# 03_-_28PINS_SCHEMATIC.net
KiCad netlist of a schematic drawn in Altium Designer
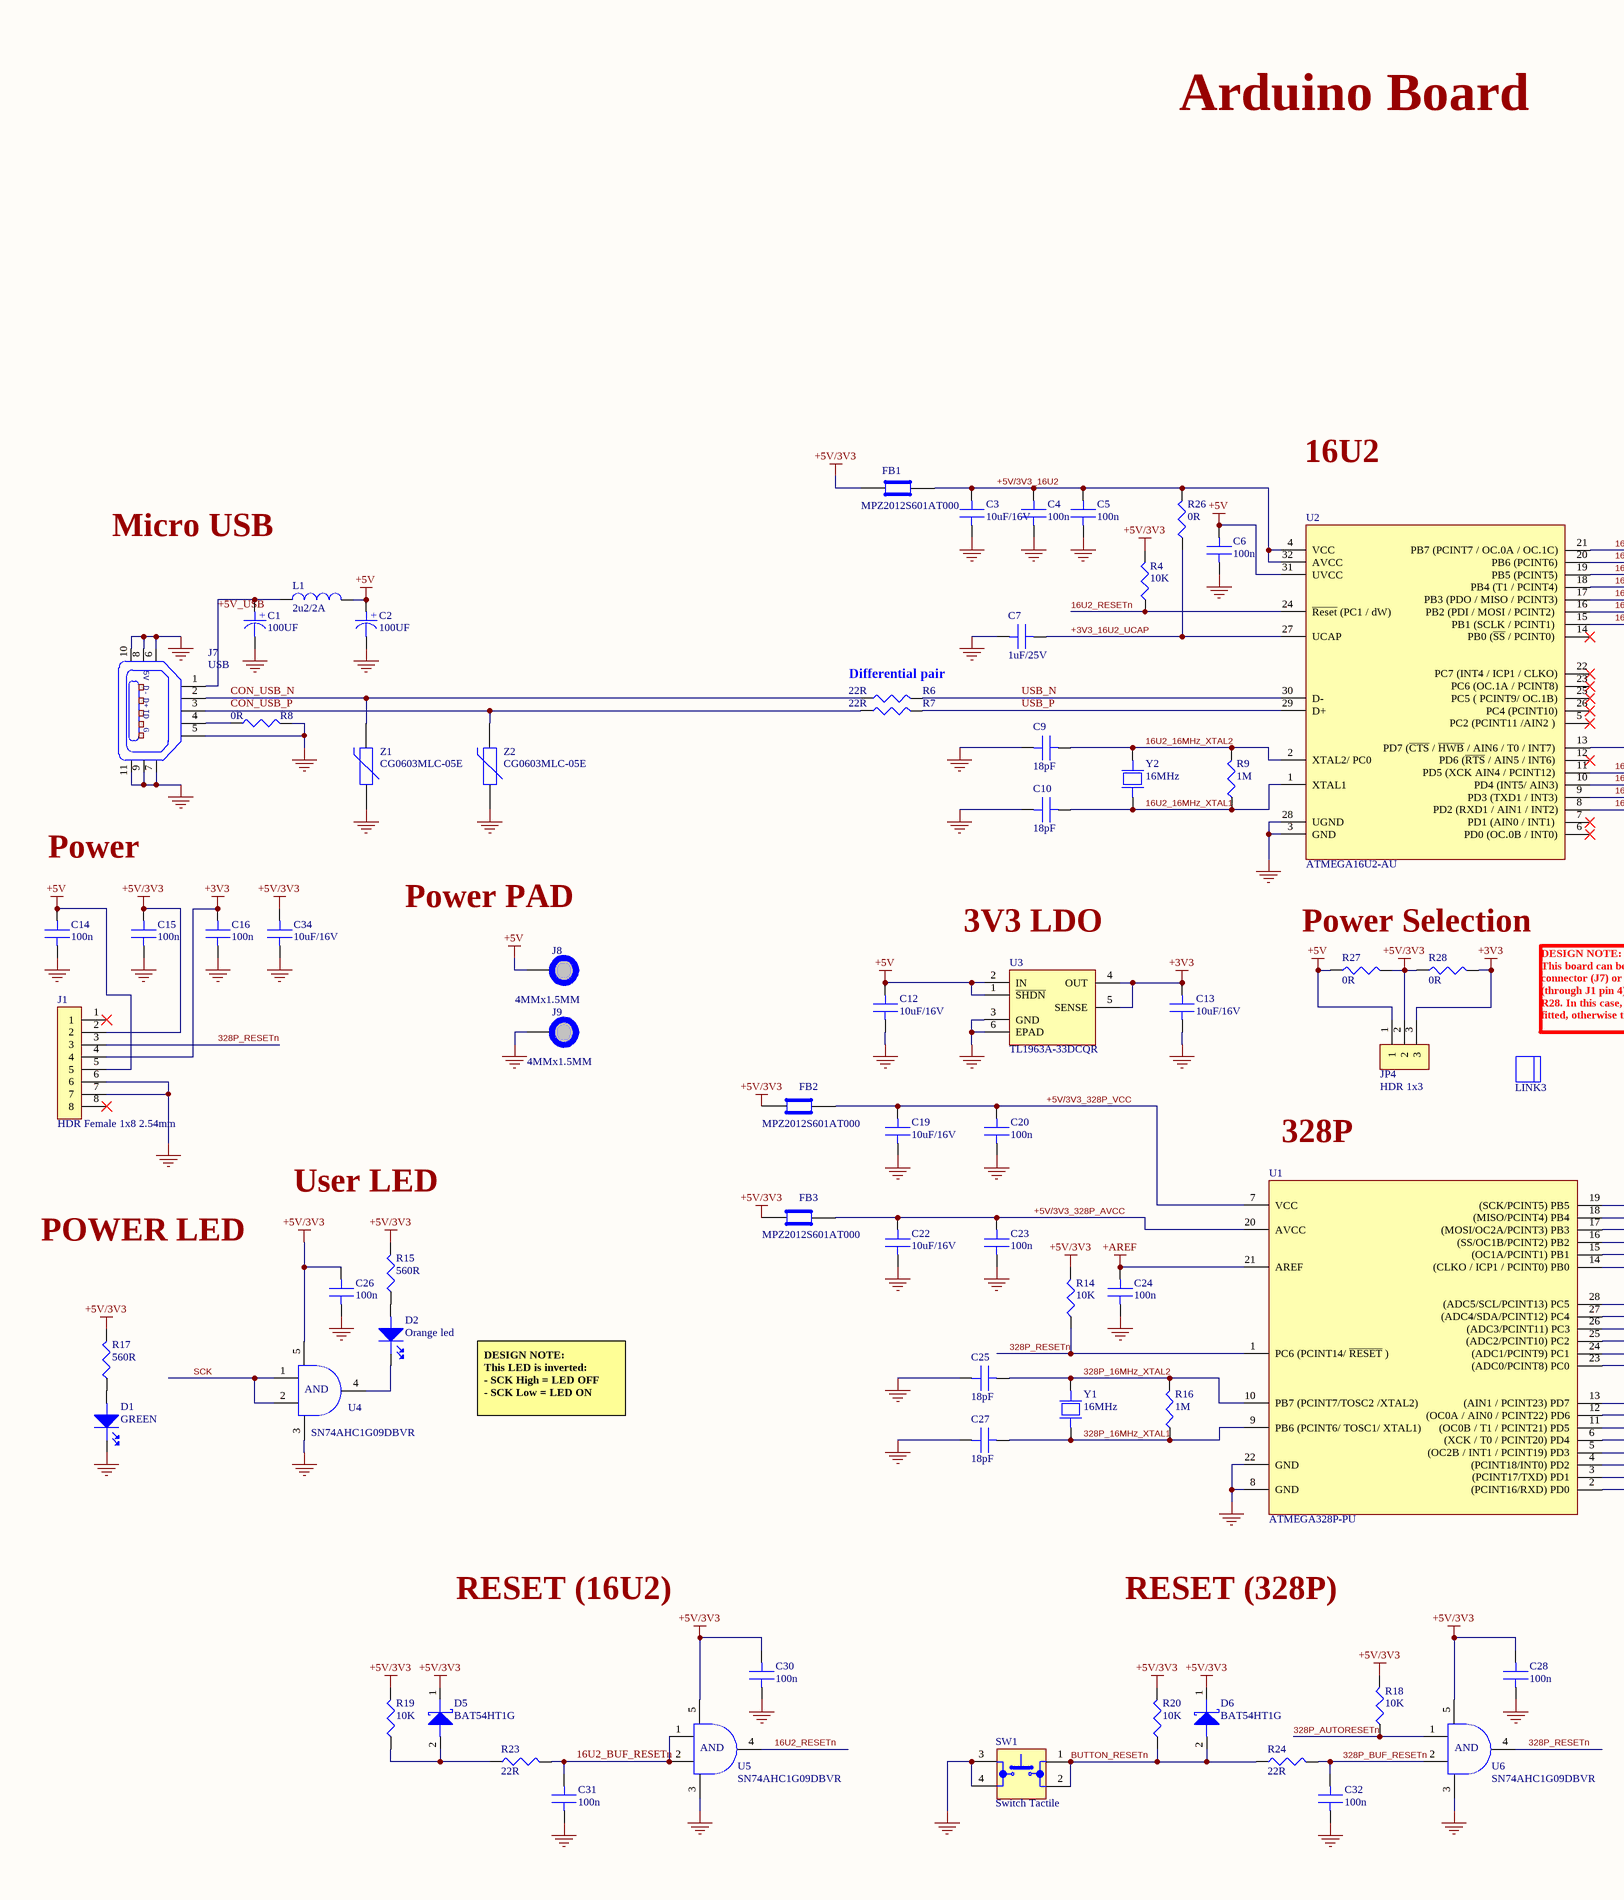
[diagram p0: [03] - 28PINS SCHEMATIC.SchDoc, left]
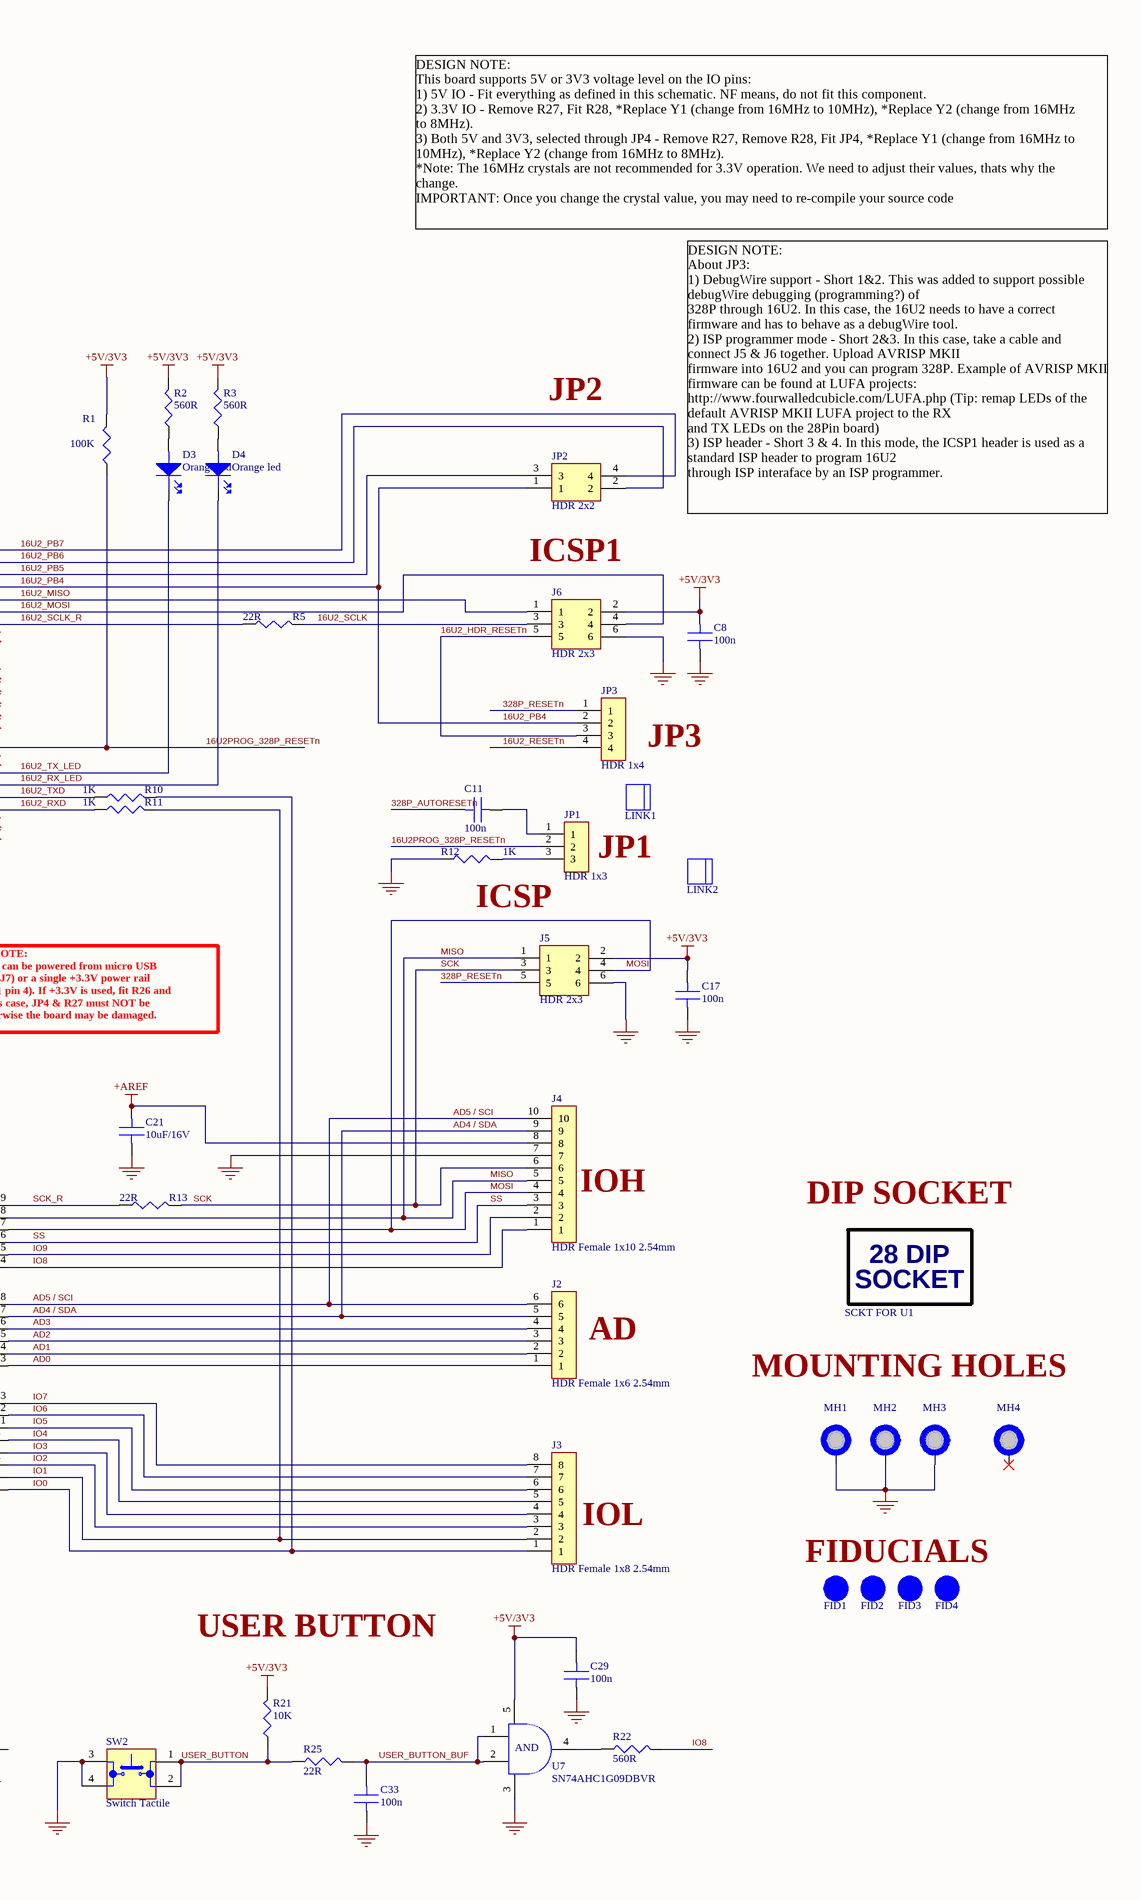
[diagram p1: [03] - 28PINS SCHEMATIC.SchDoc, right]

(export (version "E")
  (design (tool "Eeschema 10.0.6"))
  (components
    (comp (ref "C1")
      (value "100UF")
      (footprint "Capacitor")
      (description "CAP ALUM 100UF 20% 10V SMD")
      (fields
        (field (name "MANUFACTURER") "Panasonic")
        (field (name "MANUFACTURER PART NUMBER") "EEE-1AA101WR")
      )
      (libsource (lib "Arduino_Schlib1") (part "EEE-1AA101WR"))
    )
    (comp (ref "C2")
      (value "100UF")
      (footprint "Capacitor")
      (description "CAP ALUM 100UF 20% 10V SMD")
      (fields
        (field (name "MANUFACTURER") "Panasonic")
        (field (name "MANUFACTURER PART NUMBER") "EEE-1AA101WR")
      )
      (libsource (lib "Arduino_Schlib1") (part "EEE-1AA101WR"))
    )
    (comp (ref "C3")
      (value "10uF/16V")
      (footprint "C0805")
      (fields
        (field (name "MANUFACTURER") "TDK")
        (field (name "MANUFACTURER PART NUMBER") "C2012X5R1C106M085AC")
        (field (name "TOLERANCE") "20%")
      )
      (libsource (lib "Arduino_Schlib1") (part "C2012X5R1C106M085AC"))
    )
    (comp (ref "C4")
      (value "100n")
      (footprint "C0805")
      (description "100nF C Series 0805 0.1 uF 50 V ±10 % Tolerance X7R SMT Multilayer Ceramic Capacitor")
      (fields
        (field (name "MANUFACTURER") "TDK")
        (field (name "MANUFACTURER PART NUMBER") "C2012X7R1H104K085AA")
      )
      (libsource (lib "Arduino_Schlib1") (part "C2012X7R1H104K085AA"))
    )
    (comp (ref "C5")
      (value "100n")
      (footprint "C0805")
      (description "100nF C Series 0805 0.1 uF 50 V ±10 % Tolerance X7R SMT Multilayer Ceramic Capacitor")
      (fields
        (field (name "MANUFACTURER") "TDK")
        (field (name "MANUFACTURER PART NUMBER") "C2012X7R1H104K085AA")
      )
      (libsource (lib "Arduino_Schlib1") (part "C2012X7R1H104K085AA"))
    )
    (comp (ref "C6")
      (value "100n")
      (footprint "C0805")
      (description "100nF C Series 0805 0.1 uF 50 V ±10 % Tolerance X7R SMT Multilayer Ceramic Capacitor")
      (fields
        (field (name "MANUFACTURER") "TDK")
        (field (name "MANUFACTURER PART NUMBER") "C2012X7R1H104K085AA")
      )
      (libsource (lib "Arduino_Schlib1") (part "C2012X7R1H104K085AA"))
    )
    (comp (ref "C7")
      (value "1uF/25V")
      (footprint "C0805")
      (fields
        (field (name "MANUFACTURER") "TDK")
        (field (name "MANUFACTURER PART NUMBER") "C2012X5R1E105K125AA")
        (field (name "TOLERANCE") "10%")
      )
      (libsource (lib "Arduino_Schlib1") (part "C2012X5R1E105K125AA"))
    )
    (comp (ref "C8")
      (value "100n")
      (footprint "C0805")
      (description "100nF C Series 0805 0.1 uF 50 V ±10 % Tolerance X7R SMT Multilayer Ceramic Capacitor")
      (fields
        (field (name "MANUFACTURER") "TDK")
        (field (name "MANUFACTURER PART NUMBER") "C2012X7R1H104K085AA")
      )
      (libsource (lib "Arduino_Schlib1") (part "C2012X7R1H104K085AA"))
    )
    (comp (ref "C9")
      (value "18pF")
      (footprint "C0805")
      (description "18pF Cap Ceramic 18pF 50V C0G 5% SMD 0805 125C Paper T/R")
      (fields
        (field (name "MANUFACTURER") "KEMET")
        (field (name "MANUFACTURER PART NUMBER") "C0805C180J5GACTU")
      )
      (libsource (lib "Arduino_Schlib1") (part "C0805C180J5GACTU"))
    )
    (comp (ref "C10")
      (value "18pF")
      (footprint "C0805")
      (description "18pF Cap Ceramic 18pF 50V C0G 5% SMD 0805 125C Paper T/R")
      (fields
        (field (name "MANUFACTURER") "KEMET")
        (field (name "MANUFACTURER PART NUMBER") "C0805C180J5GACTU")
      )
      (libsource (lib "Arduino_Schlib1") (part "C0805C180J5GACTU"))
    )
    (comp (ref "C11")
      (value "100n")
      (footprint "C0805")
      (description "100nF C Series 0805 0.1 uF 50 V ±10 % Tolerance X7R SMT Multilayer Ceramic Capacitor")
      (fields
        (field (name "MANUFACTURER") "TDK")
        (field (name "MANUFACTURER PART NUMBER") "C2012X7R1H104K085AA")
      )
      (libsource (lib "Arduino_Schlib1") (part "C2012X7R1H104K085AA"))
    )
    (comp (ref "C12")
      (value "10uF/16V")
      (footprint "C0805")
      (fields
        (field (name "MANUFACTURER") "TDK")
        (field (name "MANUFACTURER PART NUMBER") "C2012X5R1C106M085AC")
        (field (name "TOLERANCE") "20%")
      )
      (libsource (lib "Arduino_Schlib1") (part "C2012X5R1C106M085AC"))
    )
    (comp (ref "C13")
      (value "10uF/16V")
      (footprint "C0805")
      (fields
        (field (name "MANUFACTURER") "TDK")
        (field (name "MANUFACTURER PART NUMBER") "C2012X5R1C106M085AC")
        (field (name "TOLERANCE") "20%")
      )
      (libsource (lib "Arduino_Schlib1") (part "C2012X5R1C106M085AC"))
    )
    (comp (ref "C14")
      (value "100n")
      (footprint "C0805")
      (description "100nF C Series 0805 0.1 uF 50 V ±10 % Tolerance X7R SMT Multilayer Ceramic Capacitor")
      (fields
        (field (name "MANUFACTURER") "TDK")
        (field (name "MANUFACTURER PART NUMBER") "C2012X7R1H104K085AA")
      )
      (libsource (lib "Arduino_Schlib1") (part "C2012X7R1H104K085AA"))
    )
    (comp (ref "C15")
      (value "100n")
      (footprint "C0805")
      (description "100nF C Series 0805 0.1 uF 50 V ±10 % Tolerance X7R SMT Multilayer Ceramic Capacitor")
      (fields
        (field (name "MANUFACTURER") "TDK")
        (field (name "MANUFACTURER PART NUMBER") "C2012X7R1H104K085AA")
      )
      (libsource (lib "Arduino_Schlib1") (part "C2012X7R1H104K085AA"))
    )
    (comp (ref "C16")
      (value "100n")
      (footprint "C0805")
      (description "100nF C Series 0805 0.1 uF 50 V ±10 % Tolerance X7R SMT Multilayer Ceramic Capacitor")
      (fields
        (field (name "MANUFACTURER") "TDK")
        (field (name "MANUFACTURER PART NUMBER") "C2012X7R1H104K085AA")
      )
      (libsource (lib "Arduino_Schlib1") (part "C2012X7R1H104K085AA"))
    )
    (comp (ref "C17")
      (value "100n")
      (footprint "C0805")
      (description "100nF C Series 0805 0.1 uF 50 V ±10 % Tolerance X7R SMT Multilayer Ceramic Capacitor")
      (fields
        (field (name "MANUFACTURER") "TDK")
        (field (name "MANUFACTURER PART NUMBER") "C2012X7R1H104K085AA")
      )
      (libsource (lib "Arduino_Schlib1") (part "C2012X7R1H104K085AA"))
    )
    (comp (ref "C19")
      (value "10uF/16V")
      (footprint "C0805")
      (fields
        (field (name "MANUFACTURER") "TDK")
        (field (name "MANUFACTURER PART NUMBER") "C2012X5R1C106M085AC")
        (field (name "TOLERANCE") "20%")
      )
      (libsource (lib "Arduino_Schlib1") (part "C2012X5R1C106M085AC"))
    )
    (comp (ref "C20")
      (value "100n")
      (footprint "C0805")
      (description "100nF C Series 0805 0.1 uF 50 V ±10 % Tolerance X7R SMT Multilayer Ceramic Capacitor")
      (fields
        (field (name "MANUFACTURER") "TDK")
        (field (name "MANUFACTURER PART NUMBER") "C2012X7R1H104K085AA")
      )
      (libsource (lib "Arduino_Schlib1") (part "C2012X7R1H104K085AA"))
    )
    (comp (ref "C21")
      (value "10uF/16V")
      (footprint "C0805")
      (fields
        (field (name "MANUFACTURER") "TDK")
        (field (name "MANUFACTURER PART NUMBER") "C2012X5R1C106M085AC")
        (field (name "TOLERANCE") "20%")
      )
      (libsource (lib "Arduino_Schlib1") (part "C2012X5R1C106M085AC"))
    )
    (comp (ref "C22")
      (value "10uF/16V")
      (footprint "C0805")
      (fields
        (field (name "MANUFACTURER") "TDK")
        (field (name "MANUFACTURER PART NUMBER") "C2012X5R1C106M085AC")
        (field (name "TOLERANCE") "20%")
      )
      (libsource (lib "Arduino_Schlib1") (part "C2012X5R1C106M085AC"))
    )
    (comp (ref "C23")
      (value "100n")
      (footprint "C0805")
      (description "100nF C Series 0805 0.1 uF 50 V ±10 % Tolerance X7R SMT Multilayer Ceramic Capacitor")
      (fields
        (field (name "MANUFACTURER") "TDK")
        (field (name "MANUFACTURER PART NUMBER") "C2012X7R1H104K085AA")
      )
      (libsource (lib "Arduino_Schlib1") (part "C2012X7R1H104K085AA"))
    )
    (comp (ref "C24")
      (value "100n")
      (footprint "C0805")
      (description "100nF C Series 0805 0.1 uF 50 V ±10 % Tolerance X7R SMT Multilayer Ceramic Capacitor")
      (fields
        (field (name "MANUFACTURER") "TDK")
        (field (name "MANUFACTURER PART NUMBER") "C2012X7R1H104K085AA")
      )
      (libsource (lib "Arduino_Schlib1") (part "C2012X7R1H104K085AA"))
    )
    (comp (ref "C25")
      (value "18pF")
      (footprint "C0805")
      (description "18pF Cap Ceramic 18pF 50V C0G 5% SMD 0805 125C Paper T/R")
      (fields
        (field (name "MANUFACTURER") "KEMET")
        (field (name "MANUFACTURER PART NUMBER") "C0805C180J5GACTU")
      )
      (libsource (lib "Arduino_Schlib1") (part "C0805C180J5GACTU"))
    )
    (comp (ref "C26")
      (value "100n")
      (footprint "C0805")
      (description "100nF C Series 0805 0.1 uF 50 V ±10 % Tolerance X7R SMT Multilayer Ceramic Capacitor")
      (fields
        (field (name "MANUFACTURER") "TDK")
        (field (name "MANUFACTURER PART NUMBER") "C2012X7R1H104K085AA")
      )
      (libsource (lib "Arduino_Schlib1") (part "C2012X7R1H104K085AA"))
    )
    (comp (ref "C27")
      (value "18pF")
      (footprint "C0805")
      (description "18pF Cap Ceramic 18pF 50V C0G 5% SMD 0805 125C Paper T/R")
      (fields
        (field (name "MANUFACTURER") "KEMET")
        (field (name "MANUFACTURER PART NUMBER") "C0805C180J5GACTU")
      )
      (libsource (lib "Arduino_Schlib1") (part "C0805C180J5GACTU"))
    )
    (comp (ref "C28")
      (value "100n")
      (footprint "C0805")
      (description "100nF C Series 0805 0.1 uF 50 V ±10 % Tolerance X7R SMT Multilayer Ceramic Capacitor")
      (fields
        (field (name "MANUFACTURER") "TDK")
        (field (name "MANUFACTURER PART NUMBER") "C2012X7R1H104K085AA")
      )
      (libsource (lib "Arduino_Schlib1") (part "C2012X7R1H104K085AA"))
    )
    (comp (ref "C29")
      (value "100n")
      (footprint "C0805")
      (description "100nF C Series 0805 0.1 uF 50 V ±10 % Tolerance X7R SMT Multilayer Ceramic Capacitor")
      (fields
        (field (name "MANUFACTURER") "TDK")
        (field (name "MANUFACTURER PART NUMBER") "C2012X7R1H104K085AA")
      )
      (libsource (lib "Arduino_Schlib1") (part "C2012X7R1H104K085AA"))
    )
    (comp (ref "C30")
      (value "100n")
      (footprint "C0805")
      (description "100nF C Series 0805 0.1 uF 50 V ±10 % Tolerance X7R SMT Multilayer Ceramic Capacitor")
      (fields
        (field (name "MANUFACTURER") "TDK")
        (field (name "MANUFACTURER PART NUMBER") "C2012X7R1H104K085AA")
      )
      (libsource (lib "Arduino_Schlib1") (part "C2012X7R1H104K085AA"))
    )
    (comp (ref "C31")
      (value "100n")
      (footprint "C0805")
      (description "100nF C Series 0805 0.1 uF 50 V ±10 % Tolerance X7R SMT Multilayer Ceramic Capacitor")
      (fields
        (field (name "MANUFACTURER") "TDK")
        (field (name "MANUFACTURER PART NUMBER") "C2012X7R1H104K085AA")
      )
      (libsource (lib "Arduino_Schlib1") (part "C2012X7R1H104K085AA"))
    )
    (comp (ref "C32")
      (value "100n")
      (footprint "C0805")
      (description "100nF C Series 0805 0.1 uF 50 V ±10 % Tolerance X7R SMT Multilayer Ceramic Capacitor")
      (fields
        (field (name "MANUFACTURER") "TDK")
        (field (name "MANUFACTURER PART NUMBER") "C2012X7R1H104K085AA")
      )
      (libsource (lib "Arduino_Schlib1") (part "C2012X7R1H104K085AA"))
    )
    (comp (ref "C33")
      (value "100n")
      (footprint "C0805")
      (description "100nF C Series 0805 0.1 uF 50 V ±10 % Tolerance X7R SMT Multilayer Ceramic Capacitor")
      (fields
        (field (name "MANUFACTURER") "TDK")
        (field (name "MANUFACTURER PART NUMBER") "C2012X7R1H104K085AA")
      )
      (libsource (lib "Arduino_Schlib1") (part "C2012X7R1H104K085AA"))
    )
    (comp (ref "C34")
      (value "10uF/16V")
      (footprint "C0805")
      (fields
        (field (name "MANUFACTURER") "TDK")
        (field (name "MANUFACTURER PART NUMBER") "C2012X5R1C106M085AC")
        (field (name "TOLERANCE") "20%")
      )
      (libsource (lib "Arduino_Schlib1") (part "C2012X5R1C106M085AC"))
    )
    (comp (ref "D1")
      (value "GREEN")
      (footprint "LED_0603")
      (description "LED Single Chip Green 570nm 20mA 2-Pin 0603 T/R")
      (fields
        (field (name "MANUFACTURER") "Osram Opto")
        (field (name "MANUFACTURER PART NUMBER") "LGL29K-G2J1-24-Z")
      )
      (libsource (lib "Arduino_Schlib1") (part "LGL29K-G2J1-24-Z"))
    )
    (comp (ref "D2")
      (value "Orange led")
      (footprint "LED_0603")
      (description "Smartled Orange Lc")
      (fields
        (field (name "MANUFACTURER") "Osram Opto")
        (field (name "MANUFACTURER PART NUMBER") "LOL29K-H2K1-24-Z")
      )
      (libsource (lib "Arduino_Schlib1") (part "LOL29K-H2K1-24-Z"))
    )
    (comp (ref "D3")
      (value "Orange led")
      (footprint "LED_0603")
      (description "Smartled Orange Lc")
      (fields
        (field (name "MANUFACTURER") "Osram Opto")
        (field (name "MANUFACTURER PART NUMBER") "LOL29K-H2K1-24-Z")
      )
      (libsource (lib "Arduino_Schlib1") (part "LOL29K-H2K1-24-Z"))
    )
    (comp (ref "D4")
      (value "Orange led")
      (footprint "LED_0603")
      (description "Smartled Orange Lc")
      (fields
        (field (name "MANUFACTURER") "Osram Opto")
        (field (name "MANUFACTURER PART NUMBER") "LOL29K-H2K1-24-Z")
      )
      (libsource (lib "Arduino_Schlib1") (part "LOL29K-H2K1-24-Z"))
    )
    (comp (ref "D5")
      (value "BAT54HT1G")
      (footprint "SOD323")
      (description "BAT54HT1G VR=30V IF=200mA 10pF P=200mW")
      (fields (field (name "MANUFACTURER") "ON Semiconductor / Fairchild"))
      (libsource (lib "Arduino_Schlib1") (part "BAT54HT1G"))
    )
    (comp (ref "D6")
      (value "BAT54HT1G")
      (footprint "SOD323")
      (description "BAT54HT1G VR=30V IF=200mA 10pF P=200mW")
      (fields (field (name "MANUFACTURER") "ON Semiconductor / Fairchild"))
      (libsource (lib "Arduino_Schlib1") (part "BAT54HT1G"))
    )
    (comp (ref "FB1")
      (value "MPZ2012S601AT000")
      (footprint "C0805")
      (description "0805 600Ω ±25% DCR=0.1Ω 2A")
      (fields (field (name "MANUFACTURER") "TDK"))
      (libsource (lib "Arduino_Schlib1") (part "MPZ2012S601AT000"))
    )
    (comp (ref "FB2")
      (value "MPZ2012S601AT000")
      (footprint "C0805")
      (description "0805 600Ω ±25% DCR=0.1Ω 2A")
      (fields (field (name "MANUFACTURER") "TDK"))
      (libsource (lib "Arduino_Schlib1") (part "MPZ2012S601AT000"))
    )
    (comp (ref "FB3")
      (value "MPZ2012S601AT000")
      (footprint "C0805")
      (description "0805 600Ω ±25% DCR=0.1Ω 2A")
      (fields (field (name "MANUFACTURER") "TDK"))
      (libsource (lib "Arduino_Schlib1") (part "MPZ2012S601AT000"))
    )
    (comp (ref "FID1")
      (value "FID_1mmm")
      (footprint "FID_1MM")
      (description "Fiducial 40mil")
      (libsource (lib "Arduino_Schlib1") (part "FID_1MMC"))
    )
    (comp (ref "FID2")
      (value "FID_1mmm")
      (footprint "FID_1MM")
      (description "Fiducial 40mil")
      (libsource (lib "Arduino_Schlib1") (part "FID_1MMC"))
    )
    (comp (ref "FID3")
      (value "FID_1mmm")
      (footprint "FID_1MM")
      (description "Fiducial 40mil")
      (libsource (lib "Arduino_Schlib1") (part "FID_1MMC"))
    )
    (comp (ref "FID4")
      (value "FID_1mmm")
      (footprint "FID_1MM")
      (description "Fiducial 40mil")
      (libsource (lib "Arduino_Schlib1") (part "FID_1MMC"))
    )
    (comp (ref "J1")
      (value "HDR Female 1x8 2.54mm")
      (footprint "HDR_1x8")
      (fields (field (name "MANUFACTURER") "Harwin") (field (name "MANUFACTURER PART NUMBER") "M20-7820842"))
      (libsource (lib "") (part "M20-7820842_1"))
    )
    (comp (ref "J2")
      (value "HDR Female 1x6 2.54mm")
      (footprint "HDR_1x6")
      (fields (field (name "MANUFACTURER") "Harwin") (field (name "MANUFACTURER PART NUMBER") "M20-7820646"))
      (libsource (lib "Arduino_Schlib1") (part "M20-7820646"))
    )
    (comp (ref "J3")
      (value "HDR Female 1x8 2.54mm")
      (footprint "HDR_1x8")
      (fields (field (name "MANUFACTURER") "Harwin") (field (name "MANUFACTURER PART NUMBER") "M20-7820842"))
      (libsource (lib "Arduino_Schlib1") (part "M20-7820842"))
    )
    (comp (ref "J4")
      (value "HDR Female 1x10 2.54mm")
      (footprint "HDR_1x10")
      (fields (field (name "MANUFACTURER") "Harwin") (field (name "MANUFACTURER PART NUMBER") "M20-7821046"))
      (libsource (lib "Arduino_Schlib1") (part "M20-7821046"))
    )
    (comp (ref "J5")
      (value "HDR 2x3")
      (footprint "HDR 2x3 2.54mm")
      (description "HDR 2x3 Conn Unshrouded Header HDR 6 POS 2.54mm Solder ST Top Entry Thru-Hole BergStik® Bulk")
      (fields
        (field (name "MANUFACTURER") "Amphenol ICC / FCI")
        (field (name "MANUFACTURER PART NUMBER") "67997-106HLF")
      )
      (libsource (lib "Arduino_Schlib1") (part "67997-106HLF"))
    )
    (comp (ref "J6")
      (value "HDR 2x3")
      (footprint "HDR 2x3 2.54mm")
      (description "HDR 2x3 Conn Unshrouded Header HDR 6 POS 2.54mm Solder ST Top Entry Thru-Hole BergStik® Bulk")
      (fields
        (field (name "MANUFACTURER") "Amphenol ICC / FCI")
        (field (name "MANUFACTURER PART NUMBER") "67997-106HLF")
      )
      (libsource (lib "Arduino_Schlib1") (part "67997-106HLF"))
    )
    (comp (ref "J7")
      (value "USB")
      (footprint "USB_Type_B")
      (description "USB Connector FCI Right Angle Surface Mount Mount Female ; 100 V ac; 1.8A")
      (fields
        (field (name "MANUFACTURER") "Amphenol ICC / FCI")
        (field (name "MANUFACTURER PART NUMBER") "10118193-0001LF")
      )
      (libsource (lib "Arduino_Schlib1") (part "10118193-0001LF"))
    )
    (comp (ref "J8")
      (value "4MMx1.5MM")
      (footprint "Pad_With_hole_4MMx1.5MM")
      (description "Pad with hole")
      (libsource (lib "Arduino_Schlib1") (part "Pad_with_Hole_4MMx1.5MM"))
    )
    (comp (ref "J9")
      (value "4MMx1.5MM")
      (footprint "Pad_With_hole_4MMx1.5MM")
      (description "Pad with hole")
      (libsource (lib "Arduino_Schlib1") (part "Pad_with_Hole_4MMx1.5MM"))
    )
    (comp (ref "JP1")
      (value "HDR 1x3")
      (footprint "HDR_1x3")
      (fields
        (field (name "MANUFACTURER") "Amphenol ICC / FCI")
        (field (name "MANUFACTURER PART NUMBER") "68000-103HLF")
      )
      (libsource (lib "Arduino_Schlib1") (part "68000-103HLF"))
    )
    (comp (ref "JP2")
      (value "HDR 2x2")
      (footprint "HDR 2x2 2.54mm")
      (description "HDR 2x2 Conn Unshrouded Header HDR 4 POS 2.54mm Solder ST Top Entry Thru-Hole BergStik® Bulk")
      (fields
        (field (name "MANUFACTURER") "Amphenol ICC / FCI")
        (field (name "MANUFACTURER PART NUMBER") "68602-204HLF")
      )
      (libsource (lib "Arduino_Schlib1") (part "68602-204HLF"))
    )
    (comp (ref "JP3")
      (value "HDR 1x4")
      (footprint "HDR_1x4")
      (description "HDR 1x4 Conn Unshrouded Header HDR 4 POS 2.54mm Solder ST Thru-Hole Bag")
      (fields
        (field (name "MANUFACTURER") "Amphenol ICC")
        (field (name "MANUFACTURER PART NUMBER") "68001-204HLF")
      )
      (libsource (lib "Arduino_Schlib1") (part "68001-204HLF"))
    )
    (comp (ref "JP4")
      (value "HDR 1x3")
      (footprint "HDR_1x3")
      (fields
        (field (name "MANUFACTURER") "Amphenol ICC / FCI")
        (field (name "MANUFACTURER PART NUMBER") "68000-103HLF")
      )
      (libsource (lib "") (part "68000-103HLF_1"))
    )
    (comp (ref "L1")
      (value "2u2/2A")
      (footprint "C1210_INDUCTOR")
      (description "Inductor RF Chip Wirewound 2.2uH 20% 100KHz 1.13A 0.104Ohm DCR 1210 T/R")
      (fields
        (field (name "MANUFACTURER") "KEMET")
        (field (name "MANUFACTURER PART NUMBER") "L1210R2R2MDWIT")
      )
      (libsource (lib "Arduino_Schlib1") (part "L1210R2R2MDWIT"))
    )
    (comp (ref "LINK1")
      (value "LINK")
      (description "2 Position 2.54 mm Centerline Single Circuit Open Top Jumper")
      (fields
        (field (name "MANUFACTURER") "Sullins")
        (field (name "MANUFACTURER PART NUMBER") "QPC02SXGN-RC")
      )
      (libsource (lib "Arduino_Schlib1") (part "QPC02SXGN-RC"))
    )
    (comp (ref "LINK2")
      (value "LINK")
      (description "2 Position 2.54 mm Centerline Single Circuit Open Top Jumper")
      (fields
        (field (name "MANUFACTURER") "Sullins")
        (field (name "MANUFACTURER PART NUMBER") "QPC02SXGN-RC")
      )
      (libsource (lib "Arduino_Schlib1") (part "QPC02SXGN-RC"))
    )
    (comp (ref "LINK3")
      (value "LINK")
      (description "2 Position 2.54 mm Centerline Single Circuit Open Top Jumper")
      (fields
        (field (name "MANUFACTURER") "Sullins")
        (field (name "MANUFACTURER PART NUMBER") "QPC02SXGN-RC")
      )
      (libsource (lib "Arduino_Schlib1") (part "QPC02SXGN-RC"))
    )
    (comp (ref "MH1")
      (value "MH_7.4MMC_3,2MMD")
      (footprint "MH_7.4MMC_3.2MMD")
      (libsource (lib "Arduino_Schlib1") (part "Mounting_Hole_7.4mmx3.2mm"))
    )
    (comp (ref "MH2")
      (value "MH_7.4MMC_3,2MMD")
      (footprint "MH_7.4MMC_3.2MMD")
      (libsource (lib "Arduino_Schlib1") (part "Mounting_Hole_7.4mmx3.2mm"))
    )
    (comp (ref "MH3")
      (value "MH_7.4MMC_3,2MMD")
      (footprint "MH_7.4MMC_3.2MMD")
      (libsource (lib "Arduino_Schlib1") (part "Mounting_Hole_7.4mmx3.2mm"))
    )
    (comp (ref "MH4")
      (value "MH_7.4MMC_3.3MMD NP")
      (footprint "MH_7.4MMC_3.2MMD_NP")
      (description "Mounting hole non plate")
      (libsource (lib "Arduino_Schlib1") (part "MH_7.4MMC_3.2MMD non Plate"))
    )
    (comp (ref "R1")
      (value "100K")
      (footprint "R0805")
      (description "100K Res Thick Film 0805 100K Ohm 1% 1/8W ±100ppm/°C Molded SMD Paper T/R")
      (fields
        (field (name "MANUFACTURER") "Yageo")
        (field (name "MANUFACTURER PART NUMBER") "RC0805FR-07100KL")
      )
      (libsource (lib "Arduino_Schlib1") (part "RC0805FR-07100KL"))
    )
    (comp (ref "R2")
      (value "560R")
      (footprint "R0805")
      (description "560 Ohm Res General Purpose Thick Film 0805 560 Ohm 1% 1/8W ±100ppm/°C Molded Paper T/R")
      (fields
        (field (name "MANUFACTURER") "Yageo")
        (field (name "MANUFACTURER PART NUMBER") "RC0805FR-07560RL")
      )
      (libsource (lib "Arduino_Schlib1") (part "RC0805FR-07560RL"))
    )
    (comp (ref "R3")
      (value "560R")
      (footprint "R0805")
      (description "560 Ohm Res General Purpose Thick Film 0805 560 Ohm 1% 1/8W ±100ppm/°C Molded Paper T/R")
      (fields
        (field (name "MANUFACTURER") "Yageo")
        (field (name "MANUFACTURER PART NUMBER") "RC0805FR-07560RL")
      )
      (libsource (lib "Arduino_Schlib1") (part "RC0805FR-07560RL"))
    )
    (comp (ref "R4")
      (value "10K")
      (footprint "R0805")
      (description "10K  Res Thick Film 0805 10K Ohm 1% 0.125W(1/8W) +/-100ppm/C Epoxy Pad SMD T/R")
      (fields
        (field (name "MANUFACTURER") "Yageo")
        (field (name "MANUFACTURER PART NUMBER") "RC0805FR-0710KL")
      )
      (libsource (lib "Arduino_Schlib1") (part "RC0805FR-0710KL"))
    )
    (comp (ref "R5")
      (value "22R")
      (footprint "R0805")
      (description "22R Res Thick Film 0805 22 Ohm 1% 0.125W(1/8W) ±100ppm/C Pad SMD T/R")
      (fields
        (field (name "MANUFACTURER") "Yageo")
        (field (name "MANUFACTURER PART NUMBER") "RC0805FR-0722RL")
      )
      (libsource (lib "Arduino_Schlib1") (part "RC0805FR-0722RL"))
    )
    (comp (ref "R6")
      (value "22R")
      (footprint "R0805")
      (description "22R Res Thick Film 0805 22 Ohm 1% 0.125W(1/8W) ±100ppm/C Pad SMD T/R")
      (fields
        (field (name "MANUFACTURER") "Yageo")
        (field (name "MANUFACTURER PART NUMBER") "RC0805FR-0722RL")
      )
      (libsource (lib "Arduino_Schlib1") (part "RC0805FR-0722RL"))
    )
    (comp (ref "R7")
      (value "22R")
      (footprint "R0805")
      (description "22R Res Thick Film 0805 22 Ohm 1% 0.125W(1/8W) ±100ppm/C Pad SMD T/R")
      (fields
        (field (name "MANUFACTURER") "Yageo")
        (field (name "MANUFACTURER PART NUMBER") "RC0805FR-0722RL")
      )
      (libsource (lib "Arduino_Schlib1") (part "RC0805FR-0722RL"))
    )
    (comp (ref "R8")
      (value "0R")
      (footprint "R0805")
      (description "0R Surface Mount Thick Film Resistor, RC Series, 125 mW, - 5%, 150 V, 0805 [2012 Metric]")
      (fields
        (field (name "MANUFACTURER") "Yageo")
        (field (name "MANUFACTURER PART NUMBER") "RC0805JR-070RL")
      )
      (libsource (lib "Arduino_Schlib1") (part "RC0805JR-070RL"))
    )
    (comp (ref "R9")
      (value "1M")
      (footprint "R0805")
      (description "1M Res Thick Film 0805 1M Ohm 1% 0.125W(1/8W) ±100ppm/C Pad SMD T/R")
      (fields
        (field (name "MANUFACTURER") "Yageo")
        (field (name "MANUFACTURER PART NUMBER") "RC0805FR-071ML")
      )
      (libsource (lib "Arduino_Schlib1") (part "RC0805FR-071ML"))
    )
    (comp (ref "R10")
      (value "1K")
      (footprint "R0805")
      (description "1K RES SMD 1K OHM 1% 1/8W 0805")
      (fields
        (field (name "MANUFACTURER") "Yageo")
        (field (name "MANUFACTURER PART NUMBER") "RC0805FR-071KL")
      )
      (libsource (lib "Arduino_Schlib1") (part "RC0805FR-071KL"))
    )
    (comp (ref "R11")
      (value "1K")
      (footprint "R0805")
      (description "1K RES SMD 1K OHM 1% 1/8W 0805")
      (fields
        (field (name "MANUFACTURER") "Yageo")
        (field (name "MANUFACTURER PART NUMBER") "RC0805FR-071KL")
      )
      (libsource (lib "Arduino_Schlib1") (part "RC0805FR-071KL"))
    )
    (comp (ref "R12")
      (value "1K")
      (footprint "R0805")
      (description "1K RES SMD 1K OHM 1% 1/8W 0805")
      (fields
        (field (name "MANUFACTURER") "Yageo")
        (field (name "MANUFACTURER PART NUMBER") "RC0805FR-071KL")
      )
      (libsource (lib "Arduino_Schlib1") (part "RC0805FR-071KL"))
    )
    (comp (ref "R13")
      (value "22R")
      (footprint "R0805")
      (description "22R Res Thick Film 0805 22 Ohm 1% 0.125W(1/8W) ±100ppm/C Pad SMD T/R")
      (fields
        (field (name "MANUFACTURER") "Yageo")
        (field (name "MANUFACTURER PART NUMBER") "RC0805FR-0722RL")
      )
      (libsource (lib "Arduino_Schlib1") (part "RC0805FR-0722RL"))
    )
    (comp (ref "R14")
      (value "10K")
      (footprint "R0805")
      (description "10K  Res Thick Film 0805 10K Ohm 1% 0.125W(1/8W) +/-100ppm/C Epoxy Pad SMD T/R")
      (fields
        (field (name "MANUFACTURER") "Yageo")
        (field (name "MANUFACTURER PART NUMBER") "RC0805FR-0710KL")
      )
      (libsource (lib "Arduino_Schlib1") (part "RC0805FR-0710KL"))
    )
    (comp (ref "R15")
      (value "560R")
      (footprint "R0805")
      (description "560 Ohm Res General Purpose Thick Film 0805 560 Ohm 1% 1/8W ±100ppm/°C Molded Paper T/R")
      (fields
        (field (name "MANUFACTURER") "Yageo")
        (field (name "MANUFACTURER PART NUMBER") "RC0805FR-07560RL")
      )
      (libsource (lib "Arduino_Schlib1") (part "RC0805FR-07560RL"))
    )
    (comp (ref "R16")
      (value "1M")
      (footprint "R0805")
      (description "1M Res Thick Film 0805 1M Ohm 1% 0.125W(1/8W) ±100ppm/C Pad SMD T/R")
      (fields
        (field (name "MANUFACTURER") "Yageo")
        (field (name "MANUFACTURER PART NUMBER") "RC0805FR-071ML")
      )
      (libsource (lib "Arduino_Schlib1") (part "RC0805FR-071ML"))
    )
    (comp (ref "R17")
      (value "560R")
      (footprint "R0805")
      (description "560 Ohm Res General Purpose Thick Film 0805 560 Ohm 1% 1/8W ±100ppm/°C Molded Paper T/R")
      (fields
        (field (name "MANUFACTURER") "Yageo")
        (field (name "MANUFACTURER PART NUMBER") "RC0805FR-07560RL")
      )
      (libsource (lib "Arduino_Schlib1") (part "RC0805FR-07560RL"))
    )
    (comp (ref "R18")
      (value "10K")
      (footprint "R0805")
      (description "10K  Res Thick Film 0805 10K Ohm 1% 0.125W(1/8W) +/-100ppm/C Epoxy Pad SMD T/R")
      (fields
        (field (name "MANUFACTURER") "Yageo")
        (field (name "MANUFACTURER PART NUMBER") "RC0805FR-0710KL")
      )
      (libsource (lib "Arduino_Schlib1") (part "RC0805FR-0710KL"))
    )
    (comp (ref "R19")
      (value "10K")
      (footprint "R0805")
      (description "10K  Res Thick Film 0805 10K Ohm 1% 0.125W(1/8W) +/-100ppm/C Epoxy Pad SMD T/R")
      (fields
        (field (name "MANUFACTURER") "Yageo")
        (field (name "MANUFACTURER PART NUMBER") "RC0805FR-0710KL")
      )
      (libsource (lib "Arduino_Schlib1") (part "RC0805FR-0710KL"))
    )
    (comp (ref "R20")
      (value "10K")
      (footprint "R0805")
      (description "10K  Res Thick Film 0805 10K Ohm 1% 0.125W(1/8W) +/-100ppm/C Epoxy Pad SMD T/R")
      (fields
        (field (name "MANUFACTURER") "Yageo")
        (field (name "MANUFACTURER PART NUMBER") "RC0805FR-0710KL")
      )
      (libsource (lib "Arduino_Schlib1") (part "RC0805FR-0710KL"))
    )
    (comp (ref "R21")
      (value "10K")
      (footprint "R0805")
      (description "10K  Res Thick Film 0805 10K Ohm 1% 0.125W(1/8W) +/-100ppm/C Epoxy Pad SMD T/R")
      (fields
        (field (name "MANUFACTURER") "Yageo")
        (field (name "MANUFACTURER PART NUMBER") "RC0805FR-0710KL")
      )
      (libsource (lib "Arduino_Schlib1") (part "RC0805FR-0710KL"))
    )
    (comp (ref "R22")
      (value "560R")
      (footprint "R0805")
      (description "560 Ohm Res General Purpose Thick Film 0805 560 Ohm 1% 1/8W ±100ppm/°C Molded Paper T/R")
      (fields
        (field (name "MANUFACTURER") "Yageo")
        (field (name "MANUFACTURER PART NUMBER") "RC0805FR-07560RL")
      )
      (libsource (lib "Arduino_Schlib1") (part "RC0805FR-07560RL"))
    )
    (comp (ref "R23")
      (value "22R")
      (footprint "R0805")
      (description "22R Res Thick Film 0805 22 Ohm 1% 0.125W(1/8W) ±100ppm/C Pad SMD T/R")
      (fields
        (field (name "MANUFACTURER") "Yageo")
        (field (name "MANUFACTURER PART NUMBER") "RC0805FR-0722RL")
      )
      (libsource (lib "Arduino_Schlib1") (part "RC0805FR-0722RL"))
    )
    (comp (ref "R24")
      (value "22R")
      (footprint "R0805")
      (description "22R Res Thick Film 0805 22 Ohm 1% 0.125W(1/8W) ±100ppm/C Pad SMD T/R")
      (fields
        (field (name "MANUFACTURER") "Yageo")
        (field (name "MANUFACTURER PART NUMBER") "RC0805FR-0722RL")
      )
      (libsource (lib "Arduino_Schlib1") (part "RC0805FR-0722RL"))
    )
    (comp (ref "R25")
      (value "22R")
      (footprint "R0805")
      (description "22R Res Thick Film 0805 22 Ohm 1% 0.125W(1/8W) ±100ppm/C Pad SMD T/R")
      (fields
        (field (name "MANUFACTURER") "Yageo")
        (field (name "MANUFACTURER PART NUMBER") "RC0805FR-0722RL")
      )
      (libsource (lib "Arduino_Schlib1") (part "RC0805FR-0722RL"))
    )
    (comp (ref "R26")
      (value "0R")
      (footprint "R0805")
      (description "0R Surface Mount Thick Film Resistor, RC Series, 125 mW, - 5%, 150 V, 0805 [2012 Metric]")
      (fields
        (field (name "MANUFACTURER") "Yageo")
        (field (name "MANUFACTURER PART NUMBER") "RC0805JR-070RL")
      )
      (libsource (lib "Arduino_Schlib1") (part "RC0805JR-070RL"))
    )
    (comp (ref "R27")
      (value "0R")
      (footprint "R0805")
      (description "0R Surface Mount Thick Film Resistor, RC Series, 125 mW, - 5%, 150 V, 0805 [2012 Metric]")
      (fields
        (field (name "MANUFACTURER") "Yageo")
        (field (name "MANUFACTURER PART NUMBER") "RC0805JR-070RL")
      )
      (libsource (lib "Arduino_Schlib1") (part "RC0805JR-070RL"))
    )
    (comp (ref "R28")
      (value "0R")
      (footprint "R0805")
      (description "0R Surface Mount Thick Film Resistor, RC Series, 125 mW, - 5%, 150 V, 0805 [2012 Metric]")
      (fields
        (field (name "MANUFACTURER") "Yageo")
        (field (name "MANUFACTURER PART NUMBER") "RC0805JR-070RL")
      )
      (libsource (lib "Arduino_Schlib1") (part "RC0805JR-070RL"))
    )
    (comp (ref "SCKT FOR U1")
      (value "28 dip shocket")
      (footprint "28_DIP_7.62mm_SOCKET")
      (description "Socket DIP 28Cnts DualWipe 0.3InSpc. PhosphorBronze Nickel KinkedTail 4800Series")
      (fields (field (name "MANUFACTURER") "3M") (field (name "MANUFACTURER PART NUMBER") "4828-3004-CP"))
      (libsource (lib "Arduino_Schlib1") (part "4828-3004-CP"))
    )
    (comp (ref "SW1")
      (value "Switch Tactile")
      (footprint "Switch")
      (description "Switch Tactile OFF (ON) SPST Round Button PC Pins 0.05A 24VDC 1.57N Thru-Hole Loose")
      (fields
        (field (name "MANUFACTURER") "TE Connectivity Alcoswitch")
        (field (name "MANUFACTURER PART NUMBER") "1825910-6")
      )
      (libsource (lib "Arduino_Schlib1") (part "1825910-6"))
    )
    (comp (ref "SW2")
      (value "Switch Tactile")
      (footprint "Switch")
      (description "Switch Tactile OFF (ON) SPST Round Button PC Pins 0.05A 24VDC 1.57N Thru-Hole Loose")
      (fields
        (field (name "MANUFACTURER") "TE Connectivity Alcoswitch")
        (field (name "MANUFACTURER PART NUMBER") "1825910-6")
      )
      (libsource (lib "Arduino_Schlib1") (part "1825910-6"))
    )
    (comp (ref "U1")
      (value "ATMEGA328P-PU")
      (footprint "DIP28_7.62mm")
      (description "ATMEGA328P-PU; 8 bit Microcontroller AVR 20MHz 1; 32kb Flash; 2kb RAM; I2C SPI 2")
      (fields (field (name "MANUFACTURER") "Microchip / Atmel"))
      (libsource (lib "Arduino_Schlib1") (part "ATMEGA328P-PU"))
    )
    (comp (ref "U2")
      (value "ATMEGA16U2-AU")
      (footprint "TQFP32")
      (description "8-bit AVR MCU, 16 KB, 512 Bytes, 16 MHz, 2.7 to 5.5V, TQFP-32, RoHS")
      (fields (field (name "MANUFACTURER") "Microchip / Atmel"))
      (libsource (lib "Arduino_Schlib1") (part "ATMEGA16U2-AU"))
    )
    (comp (ref "U3")
      (value "TL1963A-33DCQR")
      (footprint "DCQ (R-POSD-G6)")
      (description "LDO Regulator Pos 3.3V 1.5A 6-Pin(5+Tab) SOT-223 T/R")
      (fields (field (name "MANUFACTURER") "Texas Instruments"))
      (libsource (lib "Arduino_Schlib1") (part "TL1963A-33DCQR"))
    )
    (comp (ref "U4")
      (value "SN74AHC1G09DBVR")
      (footprint "SOP6_DBV")
      (description "AND gate Single 2-input, 2-V to 5.5-V AND gate with open-drain outputs 5-SOT-23 -55 to 125")
      (fields (field (name "MANUFACTURER") "Texas Instruments"))
      (libsource (lib "Arduino_Schlib1") (part "SN74AHC1G09DBVR"))
    )
    (comp (ref "U5")
      (value "SN74AHC1G09DBVR")
      (footprint "SOP6_DBV")
      (description "AND gate Single 2-input, 2-V to 5.5-V AND gate with open-drain outputs 5-SOT-23 -55 to 125")
      (fields (field (name "MANUFACTURER") "Texas Instruments"))
      (libsource (lib "Arduino_Schlib1") (part "SN74AHC1G09DBVR"))
    )
    (comp (ref "U6")
      (value "SN74AHC1G09DBVR")
      (footprint "SOP6_DBV")
      (description "AND gate Single 2-input, 2-V to 5.5-V AND gate with open-drain outputs 5-SOT-23 -55 to 125")
      (fields (field (name "MANUFACTURER") "Texas Instruments"))
      (libsource (lib "Arduino_Schlib1") (part "SN74AHC1G09DBVR"))
    )
    (comp (ref "U7")
      (value "SN74AHC1G09DBVR")
      (footprint "SOP6_DBV")
      (description "AND gate Single 2-input, 2-V to 5.5-V AND gate with open-drain outputs 5-SOT-23 -55 to 125")
      (fields (field (name "MANUFACTURER") "Texas Instruments"))
      (libsource (lib "Arduino_Schlib1") (part "SN74AHC1G09DBVR"))
    )
    (comp (ref "Y1")
      (value "16MHz")
      (footprint "ABM7_v1_BIG")
      (description "Crystal 16MHz ±20ppm (Tol) ±30ppm (Stability) 18pF FUND 50Ohm 2-Pin Mini-CSMD T/R")
      (fields
        (field (name "MANUFACTURER") "Abracon")
        (field (name "MANUFACTURER PART NUMBER") "ABM7-16.000MHZ-D2Y-T")
      )
      (libsource (lib "Arduino_Schlib1") (part "ABM7-16.000MHZ-D2Y-T"))
    )
    (comp (ref "Y2")
      (value "16MHz")
      (footprint "ABM7_v1_BIG")
      (description "Crystal 16MHz ±20ppm (Tol) ±30ppm (Stability) 18pF FUND 50Ohm 2-Pin Mini-CSMD T/R")
      (fields
        (field (name "MANUFACTURER") "Abracon")
        (field (name "MANUFACTURER PART NUMBER") "ABM7-16.000MHZ-D2Y-T")
      )
      (libsource (lib "Arduino_Schlib1") (part "ABM7-16.000MHZ-D2Y-T"))
    )
    (comp (ref "Z1")
      (value "CG0603MLC-05E")
      (footprint "0603")
      (description "ESD Suppressor Multilayer Varistor 5V Automotive 2-Pin Case 0603(1608Metric) T/R")
      (fields (field (name "MANUFACTURER") "Bourns") (field (name "VOLTAGE") "5V"))
      (libsource (lib "Arduino_Schlib1") (part "CG0603MLC-05E"))
    )
    (comp (ref "Z2")
      (value "CG0603MLC-05E")
      (footprint "0603")
      (description "ESD Suppressor Multilayer Varistor 5V Automotive 2-Pin Case 0603(1608Metric) T/R")
      (fields (field (name "MANUFACTURER") "Bourns") (field (name "VOLTAGE") "5V"))
      (libsource (lib "Arduino_Schlib1") (part "CG0603MLC-05E"))
    )
  )
  (nets
    (net (code "1") (name "+3V3") (class "Default")
      (node (ref "C13") (pin "2") (pinfunction "2_2") (pintype "passive"))
      (node (ref "C16") (pin "2") (pinfunction "2_2") (pintype "passive"))
      (node (ref "J1") (pin "4") (pinfunction "4_4") (pintype "passive"))
      (node (ref "JP4") (pin "3") (pinfunction "3_3") (pintype "passive"))
      (node (ref "R28") (pin "2") (pinfunction "2_2") (pintype "passive"))
      (node (ref "U3") (pin "4") (pinfunction "OUT_4") (pintype "passive"))
      (node (ref "U3") (pin "5") (pinfunction "SENSE_5") (pintype "passive"))
    )
    (net (code "2") (name "+5V") (class "Default")
      (node (ref "C12") (pin "2") (pinfunction "2_2") (pintype "passive"))
      (node (ref "C14") (pin "2") (pinfunction "2_2") (pintype "passive"))
      (node (ref "C2") (pin "1") (pinfunction "1_1") (pintype "passive"))
      (node (ref "C6") (pin "2") (pinfunction "2_2") (pintype "passive"))
      (node (ref "J1") (pin "5") (pinfunction "5_5") (pintype "passive"))
      (node (ref "J8") (pin "1") (pinfunction "1_1") (pintype "passive"))
      (node (ref "JP4") (pin "1") (pinfunction "1_1") (pintype "passive"))
      (node (ref "L1") (pin "2") (pinfunction "2_2") (pintype "passive"))
      (node (ref "R27") (pin "1") (pinfunction "1_1") (pintype "passive"))
      (node (ref "U2") (pin "31") (pinfunction "UVCC_31") (pintype "passive"))
      (node (ref "U3") (pin "1") (pinfunction "~{SHDN}_1") (pintype "passive"))
      (node (ref "U3") (pin "2") (pinfunction "IN_2") (pintype "passive"))
    )
    (net (code "3") (name "+5V{slash}3V3") (class "Default")
      (node (ref "C15") (pin "2") (pinfunction "2_2") (pintype "passive"))
      (node (ref "C17") (pin "2") (pinfunction "2_2") (pintype "passive"))
      (node (ref "C26") (pin "2") (pinfunction "2_2") (pintype "passive"))
      (node (ref "C28") (pin "2") (pinfunction "2_2") (pintype "passive"))
      (node (ref "C29") (pin "2") (pinfunction "2_2") (pintype "passive"))
      (node (ref "C30") (pin "2") (pinfunction "2_2") (pintype "passive"))
      (node (ref "C34") (pin "2") (pinfunction "2_2") (pintype "passive"))
      (node (ref "C8") (pin "2") (pinfunction "2_2") (pintype "passive"))
      (node (ref "D5") (pin "1") (pinfunction "Cathode_1") (pintype "passive"))
      (node (ref "D6") (pin "1") (pinfunction "Cathode_1") (pintype "passive"))
      (node (ref "FB1") (pin "1") (pinfunction "1_1") (pintype "passive"))
      (node (ref "FB2") (pin "1") (pinfunction "1_1") (pintype "passive"))
      (node (ref "FB3") (pin "1") (pinfunction "1_1") (pintype "passive"))
      (node (ref "J1") (pin "2") (pinfunction "2_2") (pintype "passive"))
      (node (ref "J5") (pin "2") (pinfunction "2_2") (pintype "passive"))
      (node (ref "J6") (pin "2") (pinfunction "2_2") (pintype "passive"))
      (node (ref "JP4") (pin "2") (pinfunction "2_2") (pintype "passive"))
      (node (ref "R1") (pin "2") (pinfunction "2_2") (pintype "passive"))
      (node (ref "R14") (pin "2") (pinfunction "2_2") (pintype "passive"))
      (node (ref "R15") (pin "2") (pinfunction "2_2") (pintype "passive"))
      (node (ref "R17") (pin "2") (pinfunction "2_2") (pintype "passive"))
      (node (ref "R18") (pin "2") (pinfunction "2_2") (pintype "passive"))
      (node (ref "R19") (pin "2") (pinfunction "2_2") (pintype "passive"))
      (node (ref "R2") (pin "2") (pinfunction "2_2") (pintype "passive"))
      (node (ref "R20") (pin "2") (pinfunction "2_2") (pintype "passive"))
      (node (ref "R21") (pin "2") (pinfunction "2_2") (pintype "passive"))
      (node (ref "R27") (pin "2") (pinfunction "2_2") (pintype "passive"))
      (node (ref "R28") (pin "1") (pinfunction "1_1") (pintype "passive"))
      (node (ref "R3") (pin "2") (pinfunction "2_2") (pintype "passive"))
      (node (ref "R4") (pin "2") (pinfunction "2_2") (pintype "passive"))
      (node (ref "U4") (pin "5") (pinfunction "5_5") (pintype "passive"))
      (node (ref "U5") (pin "5") (pinfunction "5_5") (pintype "passive"))
      (node (ref "U6") (pin "5") (pinfunction "5_5") (pintype "passive"))
      (node (ref "U7") (pin "5") (pinfunction "5_5") (pintype "passive"))
    )
    (net (code "4") (name "+AREF") (class "Default")
      (node (ref "C21") (pin "2") (pinfunction "2_2") (pintype "passive"))
      (node (ref "C24") (pin "2") (pinfunction "2_2") (pintype "passive"))
      (node (ref "J4") (pin "8") (pinfunction "8_8") (pintype "passive"))
      (node (ref "U1") (pin "21") (pinfunction "AREF_21") (pintype "passive"))
    )
    (net (code "5") (name "/+3V3_16U2_UCAP") (class "Default")
      (node (ref "C7") (pin "2") (pinfunction "2_2") (pintype "passive"))
      (node (ref "R26") (pin "1") (pinfunction "1_1") (pintype "passive"))
      (node (ref "U2") (pin "27") (pinfunction "UCAP_27") (pintype "passive"))
    )
    (net (code "6") (name "/+5V_USB") (class "Default")
      (node (ref "C1") (pin "1") (pinfunction "1_1") (pintype "passive"))
      (node (ref "J7") (pin "1") (pinfunction "1_1") (pintype "passive"))
      (node (ref "L1") (pin "1") (pinfunction "1_1") (pintype "passive"))
    )
    (net (code "7") (name "/+5V{slash}3V3_16U2") (class "Default")
      (node (ref "C3") (pin "2") (pinfunction "2_2") (pintype "passive"))
      (node (ref "C4") (pin "2") (pinfunction "2_2") (pintype "passive"))
      (node (ref "C5") (pin "2") (pinfunction "2_2") (pintype "passive"))
      (node (ref "FB1") (pin "2") (pinfunction "2_2") (pintype "passive"))
      (node (ref "R26") (pin "2") (pinfunction "2_2") (pintype "passive"))
      (node (ref "U2") (pin "32") (pinfunction "AVCC_32") (pintype "passive"))
      (node (ref "U2") (pin "4") (pinfunction "VCC_4") (pintype "passive"))
    )
    (net (code "8") (name "/+5V{slash}3V3_328P_AVCC") (class "Default")
      (node (ref "C22") (pin "2") (pinfunction "2_2") (pintype "passive"))
      (node (ref "C23") (pin "2") (pinfunction "2_2") (pintype "passive"))
      (node (ref "FB3") (pin "2") (pinfunction "2_2") (pintype "passive"))
      (node (ref "U1") (pin "20") (pinfunction "AVCC_20") (pintype "passive"))
    )
    (net (code "9") (name "/+5V{slash}3V3_328P_VCC") (class "Default")
      (node (ref "C19") (pin "2") (pinfunction "2_2") (pintype "passive"))
      (node (ref "C20") (pin "2") (pinfunction "2_2") (pintype "passive"))
      (node (ref "FB2") (pin "2") (pinfunction "2_2") (pintype "passive"))
      (node (ref "U1") (pin "7") (pinfunction "VCC_7") (pintype "passive"))
    )
    (net (code "10") (name "/16U2PROG_328P_RESETn") (class "Default")
      (node (ref "JP1") (pin "2") (pinfunction "2_2") (pintype "passive"))
      (node (ref "R1") (pin "1") (pinfunction "1_1") (pintype "passive"))
      (node (ref "U2") (pin "13") (pinfunction "PD7_(~{CTS}_/_~{HWB}_/_AIN6_/_T0_/_INT7)_13") (pintype "passive"))
    )
    (net (code "11") (name "/16U2_16MHz_XTAL1") (class "Default")
      (node (ref "C10") (pin "2") (pinfunction "2_2") (pintype "passive"))
      (node (ref "R9") (pin "1") (pinfunction "1_1") (pintype "passive"))
      (node (ref "U2") (pin "1") (pinfunction "XTAL1_1") (pintype "passive"))
      (node (ref "Y2") (pin "1") (pinfunction "1_1") (pintype "passive"))
    )
    (net (code "12") (name "/16U2_16MHz_XTAL2") (class "Default")
      (node (ref "C9") (pin "2") (pinfunction "2_2") (pintype "passive"))
      (node (ref "R9") (pin "2") (pinfunction "2_2") (pintype "passive"))
      (node (ref "U2") (pin "2") (pinfunction "XTAL2/_PC0_2") (pintype "passive"))
      (node (ref "Y2") (pin "2") (pinfunction "2_2") (pintype "passive"))
    )
    (net (code "13") (name "/16U2_BUF_RESETn") (class "Default")
      (node (ref "C31") (pin "2") (pinfunction "2_2") (pintype "passive"))
      (node (ref "R23") (pin "2") (pinfunction "2_2") (pintype "passive"))
      (node (ref "U5") (pin "1") (pinfunction "1_1") (pintype "passive"))
      (node (ref "U5") (pin "2") (pinfunction "2_2") (pintype "passive"))
    )
    (net (code "14") (name "/16U2_HDR_RESETn") (class "Default")
      (node (ref "J6") (pin "5") (pinfunction "5_5") (pintype "passive"))
      (node (ref "JP3") (pin "3") (pinfunction "3_3") (pintype "passive"))
    )
    (net (code "15") (name "/16U2_MISO") (class "Default")
      (node (ref "J6") (pin "1") (pinfunction "1_1") (pintype "passive"))
      (node (ref "U2") (pin "17") (pinfunction "PB3_(PDO_/_MISO_/_PCINT3)_17") (pintype "passive"))
    )
    (net (code "16") (name "/16U2_MOSI") (class "Default")
      (node (ref "J6") (pin "4") (pinfunction "4_4") (pintype "passive"))
      (node (ref "U2") (pin "16") (pinfunction "PB2_(PDI_/_MOSI_/_PCINT2)_16") (pintype "passive"))
    )
    (net (code "17") (name "/16U2_PB4") (class "Default")
      (node (ref "JP2") (pin "1") (pinfunction "1_1") (pintype "passive"))
      (node (ref "JP3") (pin "2") (pinfunction "2_2") (pintype "passive"))
      (node (ref "U2") (pin "18") (pinfunction "PB4_(T1_/_PCINT4)_18") (pintype "passive"))
    )
    (net (code "18") (name "/16U2_PB5") (class "Default")
      (node (ref "JP2") (pin "3") (pinfunction "3_3") (pintype "passive"))
      (node (ref "U2") (pin "19") (pinfunction "PB5_(PCINT5)_19") (pintype "passive"))
    )
    (net (code "19") (name "/16U2_PB6") (class "Default")
      (node (ref "JP2") (pin "2") (pinfunction "2_2") (pintype "passive"))
      (node (ref "U2") (pin "20") (pinfunction "PB6_(PCINT6)_20") (pintype "passive"))
    )
    (net (code "20") (name "/16U2_PB7") (class "Default")
      (node (ref "JP2") (pin "4") (pinfunction "4_4") (pintype "passive"))
      (node (ref "U2") (pin "21") (pinfunction "PB7_(PCINT7_/_OC.0A_/_OC.1C)_21") (pintype "passive"))
    )
    (net (code "21") (name "/16U2_RESETn") (class "Default")
      (node (ref "JP3") (pin "4") (pinfunction "4_4") (pintype "passive"))
      (node (ref "R4") (pin "1") (pinfunction "1_1") (pintype "passive"))
      (node (ref "U2") (pin "24") (pinfunction "~{Reset}_(PC1_/_dW)_24") (pintype "passive"))
      (node (ref "U5") (pin "4") (pinfunction "4_4") (pintype "passive"))
    )
    (net (code "22") (name "/16U2_RXD") (class "Default")
      (node (ref "R11") (pin "1") (pinfunction "1_1") (pintype "passive"))
      (node (ref "U2") (pin "8") (pinfunction "PD2_(RXD1_/_AIN1_/_INT2)_8") (pintype "passive"))
    )
    (net (code "23") (name "/16U2_RX_LED") (class "Default")
      (node (ref "D4") (pin "1") (pinfunction "Cathode_1") (pintype "passive"))
      (node (ref "U2") (pin "10") (pinfunction "PD4_(INT5/_AIN3)_10") (pintype "passive"))
    )
    (net (code "24") (name "/16U2_SCLK") (class "Default")
      (node (ref "J6") (pin "3") (pinfunction "3_3") (pintype "passive"))
      (node (ref "R5") (pin "2") (pinfunction "2_2") (pintype "passive"))
    )
    (net (code "25") (name "/16U2_SCLK_R") (class "Default")
      (node (ref "R5") (pin "1") (pinfunction "1_1") (pintype "passive"))
      (node (ref "U2") (pin "15") (pinfunction "PB1_(SCLK_/_PCINT1)_15") (pintype "passive"))
    )
    (net (code "26") (name "/16U2_TXD") (class "Default")
      (node (ref "R10") (pin "1") (pinfunction "1_1") (pintype "passive"))
      (node (ref "U2") (pin "9") (pinfunction "PD3_(TXD1_/_INT3)_9") (pintype "passive"))
    )
    (net (code "27") (name "/16U2_TX_LED") (class "Default")
      (node (ref "D3") (pin "1") (pinfunction "Cathode_1") (pintype "passive"))
      (node (ref "U2") (pin "11") (pinfunction "PD5_(XCK_AIN4_/_PCINT12)_11") (pintype "passive"))
    )
    (net (code "28") (name "/328P_16MHz_XTAL1") (class "Default")
      (node (ref "C27") (pin "2") (pinfunction "2_2") (pintype "passive"))
      (node (ref "R16") (pin "1") (pinfunction "1_1") (pintype "passive"))
      (node (ref "U1") (pin "9") (pinfunction "PB6_(PCINT6/_TOSC1/_XTAL1)_9") (pintype "passive"))
      (node (ref "Y1") (pin "1") (pinfunction "1_1") (pintype "passive"))
    )
    (net (code "29") (name "/328P_16MHz_XTAL2") (class "Default")
      (node (ref "C25") (pin "2") (pinfunction "2_2") (pintype "passive"))
      (node (ref "R16") (pin "2") (pinfunction "2_2") (pintype "passive"))
      (node (ref "U1") (pin "10") (pinfunction "PB7_(PCINT7/TOSC2_/XTAL2)_10") (pintype "passive"))
      (node (ref "Y1") (pin "2") (pinfunction "2_2") (pintype "passive"))
    )
    (net (code "30") (name "/328P_AUTORESETn") (class "Default")
      (node (ref "C11") (pin "1") (pinfunction "1_1") (pintype "passive"))
      (node (ref "R18") (pin "1") (pinfunction "1_1") (pintype "passive"))
      (node (ref "U6") (pin "1") (pinfunction "1_1") (pintype "passive"))
    )
    (net (code "31") (name "/328P_BUF_RESETn") (class "Default")
      (node (ref "C32") (pin "2") (pinfunction "2_2") (pintype "passive"))
      (node (ref "R24") (pin "2") (pinfunction "2_2") (pintype "passive"))
      (node (ref "U6") (pin "2") (pinfunction "2_2") (pintype "passive"))
    )
    (net (code "32") (name "/328P_RESETn") (class "Default")
      (node (ref "J1") (pin "3") (pinfunction "3_3") (pintype "passive"))
      (node (ref "J5") (pin "5") (pinfunction "5_5") (pintype "passive"))
      (node (ref "JP3") (pin "1") (pinfunction "1_1") (pintype "passive"))
      (node (ref "R14") (pin "1") (pinfunction "1_1") (pintype "passive"))
      (node (ref "U1") (pin "1") (pinfunction "PC6_(PCINT14/_~{RESET}_)_1") (pintype "passive"))
      (node (ref "U6") (pin "4") (pinfunction "4_4") (pintype "passive"))
    )
    (net (code "33") (name "/AD0") (class "Default")
      (node (ref "J2") (pin "1") (pinfunction "1_1") (pintype "passive"))
      (node (ref "U1") (pin "23") (pinfunction "(ADC0/PCINT8)_PC0_23") (pintype "passive"))
    )
    (net (code "34") (name "/AD1") (class "Default")
      (node (ref "J2") (pin "2") (pinfunction "2_2") (pintype "passive"))
      (node (ref "U1") (pin "24") (pinfunction "(ADC1/PCINT9)_PC1_24") (pintype "passive"))
    )
    (net (code "35") (name "/AD2") (class "Default")
      (node (ref "J2") (pin "3") (pinfunction "3_3") (pintype "passive"))
      (node (ref "U1") (pin "25") (pinfunction "(ADC2/PCINT10)_PC2_25") (pintype "passive"))
    )
    (net (code "36") (name "/AD3") (class "Default")
      (node (ref "J2") (pin "4") (pinfunction "4_4") (pintype "passive"))
      (node (ref "U1") (pin "26") (pinfunction "(ADC3/PCINT11)_PC3_26") (pintype "passive"))
    )
    (net (code "37") (name "/AD4 {slash} SDA") (class "Default")
      (node (ref "J2") (pin "5") (pinfunction "5_5") (pintype "passive"))
      (node (ref "J4") (pin "9") (pinfunction "9_9") (pintype "passive"))
      (node (ref "U1") (pin "27") (pinfunction "(ADC4/SDA/PCINT12)_PC4_27") (pintype "passive"))
    )
    (net (code "38") (name "/AD5 {slash} SCI") (class "Default")
      (node (ref "J2") (pin "6") (pinfunction "6_6") (pintype "passive"))
      (node (ref "J4") (pin "10") (pinfunction "10_10") (pintype "passive"))
      (node (ref "U1") (pin "28") (pinfunction "(ADC5/SCL/PCINT13)_PC5_28") (pintype "passive"))
    )
    (net (code "39") (name "/BUTTON_RESETn") (class "Default")
      (node (ref "D6") (pin "2") (pinfunction "Anode_2") (pintype "passive"))
      (node (ref "R20") (pin "1") (pinfunction "1_1") (pintype "passive"))
      (node (ref "R24") (pin "1") (pinfunction "1_1") (pintype "passive"))
      (node (ref "SW1") (pin "1") (pinfunction "1_1") (pintype "passive"))
      (node (ref "SW1") (pin "2") (pinfunction "2_2") (pintype "passive"))
    )
    (net (code "40") (name "/CON_USB_N") (class "Default")
      (node (ref "J7") (pin "2") (pinfunction "2_2") (pintype "passive"))
      (node (ref "R6") (pin "1") (pinfunction "1_1") (pintype "passive"))
      (node (ref "Z1") (pin "2") (pinfunction "2_2") (pintype "passive"))
    )
    (net (code "41") (name "/CON_USB_P") (class "Default")
      (node (ref "J7") (pin "3") (pinfunction "3_3") (pintype "passive"))
      (node (ref "R7") (pin "1") (pinfunction "1_1") (pintype "passive"))
      (node (ref "Z2") (pin "2") (pinfunction "2_2") (pintype "passive"))
    )
    (net (code "42") (name "/IO0") (class "Default")
      (node (ref "J3") (pin "1") (pinfunction "1_1") (pintype "passive"))
      (node (ref "R10") (pin "2") (pinfunction "2_2") (pintype "passive"))
      (node (ref "U1") (pin "2") (pinfunction "(PCINT16/RXD)_PD0_2") (pintype "passive"))
    )
    (net (code "43") (name "/IO1") (class "Default")
      (node (ref "J3") (pin "2") (pinfunction "2_2") (pintype "passive"))
      (node (ref "R11") (pin "2") (pinfunction "2_2") (pintype "passive"))
      (node (ref "U1") (pin "3") (pinfunction "(PCINT17/TXD)_PD1_3") (pintype "passive"))
    )
    (net (code "44") (name "/IO2") (class "Default")
      (node (ref "J3") (pin "3") (pinfunction "3_3") (pintype "passive"))
      (node (ref "U1") (pin "4") (pinfunction "(PCINT18/INT0)_PD2_4") (pintype "passive"))
    )
    (net (code "45") (name "/IO3") (class "Default")
      (node (ref "J3") (pin "4") (pinfunction "4_4") (pintype "passive"))
      (node (ref "U1") (pin "5") (pinfunction "(OC2B_/_INT1_/_PCINT19)_PD3_5") (pintype "passive"))
    )
    (net (code "46") (name "/IO4") (class "Default")
      (node (ref "J3") (pin "5") (pinfunction "5_5") (pintype "passive"))
      (node (ref "U1") (pin "6") (pinfunction "(XCK_/_T0_/_PCINT20)_PD4_6") (pintype "passive"))
    )
    (net (code "47") (name "/IO5") (class "Default")
      (node (ref "J3") (pin "6") (pinfunction "6_6") (pintype "passive"))
      (node (ref "U1") (pin "11") (pinfunction "(OC0B_/_T1_/_PCINT21)_PD5_11") (pintype "passive"))
    )
    (net (code "48") (name "/IO6") (class "Default")
      (node (ref "J3") (pin "7") (pinfunction "7_7") (pintype "passive"))
      (node (ref "U1") (pin "12") (pinfunction "(OC0A_/_AIN0_/_PCINT22)_PD6_12") (pintype "passive"))
    )
    (net (code "49") (name "/IO7") (class "Default")
      (node (ref "J3") (pin "8") (pinfunction "8_8") (pintype "passive"))
      (node (ref "U1") (pin "13") (pinfunction "(AIN1_/_PCINT23)_PD7_13") (pintype "passive"))
    )
    (net (code "50") (name "/IO8") (class "Default")
      (node (ref "J4") (pin "1") (pinfunction "1_1") (pintype "passive"))
      (node (ref "R22") (pin "2") (pinfunction "2_2") (pintype "passive"))
      (node (ref "U1") (pin "14") (pinfunction "(CLKO_/_ICP1_/_PCINT0)_PB0_14") (pintype "passive"))
    )
    (net (code "51") (name "/IO9") (class "Default")
      (node (ref "J4") (pin "2") (pinfunction "2_2") (pintype "passive"))
      (node (ref "U1") (pin "15") (pinfunction "(OC1A/PCINT1)_PB1_15") (pintype "passive"))
    )
    (net (code "52") (name "/MISO") (class "Default")
      (node (ref "J4") (pin "5") (pinfunction "5_5") (pintype "passive"))
      (node (ref "J5") (pin "1") (pinfunction "1_1") (pintype "passive"))
      (node (ref "U1") (pin "18") (pinfunction "(MISO/PCINT4)_PB4_18") (pintype "passive"))
    )
    (net (code "53") (name "/MOSI") (class "Default")
      (node (ref "J4") (pin "4") (pinfunction "4_4") (pintype "passive"))
      (node (ref "J5") (pin "4") (pinfunction "4_4") (pintype "passive"))
      (node (ref "U1") (pin "17") (pinfunction "(MOSI/OC2A/PCINT3)_PB3_17") (pintype "passive"))
    )
    (net (code "54") (name "/SCK") (class "Default")
      (node (ref "J4") (pin "6") (pinfunction "6_6") (pintype "passive"))
      (node (ref "J5") (pin "3") (pinfunction "3_3") (pintype "passive"))
      (node (ref "R13") (pin "2") (pinfunction "2_2") (pintype "passive"))
      (node (ref "U4") (pin "1") (pinfunction "1_1") (pintype "passive"))
      (node (ref "U4") (pin "2") (pinfunction "2_2") (pintype "passive"))
    )
    (net (code "55") (name "/SCK_R") (class "Default")
      (node (ref "R13") (pin "1") (pinfunction "1_1") (pintype "passive"))
      (node (ref "U1") (pin "19") (pinfunction "(SCK/PCINT5)_PB5_19") (pintype "passive"))
    )
    (net (code "56") (name "/SS") (class "Default")
      (node (ref "J4") (pin "3") (pinfunction "3_3") (pintype "passive"))
      (node (ref "U1") (pin "16") (pinfunction "(SS/OC1B/PCINT2)_PB2_16") (pintype "passive"))
    )
    (net (code "57") (name "/USB_N") (class "Default")
      (node (ref "R6") (pin "2") (pinfunction "2_2") (pintype "passive"))
      (node (ref "U2") (pin "30") (pinfunction "D-_30") (pintype "passive"))
    )
    (net (code "58") (name "/USB_P") (class "Default")
      (node (ref "R7") (pin "2") (pinfunction "2_2") (pintype "passive"))
      (node (ref "U2") (pin "29") (pinfunction "D+_29") (pintype "passive"))
    )
    (net (code "59") (name "/USER_BUTTON") (class "Default")
      (node (ref "R21") (pin "1") (pinfunction "1_1") (pintype "passive"))
      (node (ref "R25") (pin "1") (pinfunction "1_1") (pintype "passive"))
      (node (ref "SW2") (pin "1") (pinfunction "1_1") (pintype "passive"))
      (node (ref "SW2") (pin "2") (pinfunction "2_2") (pintype "passive"))
    )
    (net (code "60") (name "/USER_BUTTON_BUF") (class "Default")
      (node (ref "C33") (pin "2") (pinfunction "2_2") (pintype "passive"))
      (node (ref "R25") (pin "2") (pinfunction "2_2") (pintype "passive"))
      (node (ref "U7") (pin "1") (pinfunction "1_1") (pintype "passive"))
      (node (ref "U7") (pin "2") (pinfunction "2_2") (pintype "passive"))
    )
    (net (code "61") (name "GND") (class "Default")
      (node (ref "C1") (pin "2") (pinfunction "2_2") (pintype "passive"))
      (node (ref "C10") (pin "1") (pinfunction "1_1") (pintype "passive"))
      (node (ref "C12") (pin "1") (pinfunction "1_1") (pintype "passive"))
      (node (ref "C13") (pin "1") (pinfunction "1_1") (pintype "passive"))
      (node (ref "C14") (pin "1") (pinfunction "1_1") (pintype "passive"))
      (node (ref "C15") (pin "1") (pinfunction "1_1") (pintype "passive"))
      (node (ref "C16") (pin "1") (pinfunction "1_1") (pintype "passive"))
      (node (ref "C17") (pin "1") (pinfunction "1_1") (pintype "passive"))
      (node (ref "C19") (pin "1") (pinfunction "1_1") (pintype "passive"))
      (node (ref "C2") (pin "2") (pinfunction "2_2") (pintype "passive"))
      (node (ref "C20") (pin "1") (pinfunction "1_1") (pintype "passive"))
      (node (ref "C21") (pin "1") (pinfunction "1_1") (pintype "passive"))
      (node (ref "C22") (pin "1") (pinfunction "1_1") (pintype "passive"))
      (node (ref "C23") (pin "1") (pinfunction "1_1") (pintype "passive"))
      (node (ref "C24") (pin "1") (pinfunction "1_1") (pintype "passive"))
      (node (ref "C25") (pin "1") (pinfunction "1_1") (pintype "passive"))
      (node (ref "C26") (pin "1") (pinfunction "1_1") (pintype "passive"))
      (node (ref "C27") (pin "1") (pinfunction "1_1") (pintype "passive"))
      (node (ref "C28") (pin "1") (pinfunction "1_1") (pintype "passive"))
      (node (ref "C29") (pin "1") (pinfunction "1_1") (pintype "passive"))
      (node (ref "C3") (pin "1") (pinfunction "1_1") (pintype "passive"))
      (node (ref "C30") (pin "1") (pinfunction "1_1") (pintype "passive"))
      (node (ref "C31") (pin "1") (pinfunction "1_1") (pintype "passive"))
      (node (ref "C32") (pin "1") (pinfunction "1_1") (pintype "passive"))
      (node (ref "C33") (pin "1") (pinfunction "1_1") (pintype "passive"))
      (node (ref "C34") (pin "1") (pinfunction "1_1") (pintype "passive"))
      (node (ref "C4") (pin "1") (pinfunction "1_1") (pintype "passive"))
      (node (ref "C5") (pin "1") (pinfunction "1_1") (pintype "passive"))
      (node (ref "C6") (pin "1") (pinfunction "1_1") (pintype "passive"))
      (node (ref "C7") (pin "1") (pinfunction "1_1") (pintype "passive"))
      (node (ref "C8") (pin "1") (pinfunction "1_1") (pintype "passive"))
      (node (ref "C9") (pin "1") (pinfunction "1_1") (pintype "passive"))
      (node (ref "D1") (pin "1") (pinfunction "Cathode_1") (pintype "passive"))
      (node (ref "J1") (pin "6") (pinfunction "6_6") (pintype "passive"))
      (node (ref "J1") (pin "7") (pinfunction "7_7") (pintype "passive"))
      (node (ref "J4") (pin "7") (pinfunction "7_7") (pintype "passive"))
      (node (ref "J5") (pin "6") (pinfunction "6_6") (pintype "passive"))
      (node (ref "J6") (pin "6") (pinfunction "6_6") (pintype "passive"))
      (node (ref "J7") (pin "10") (pinfunction "10_10") (pintype "passive"))
      (node (ref "J7") (pin "11") (pinfunction "11_11") (pintype "passive"))
      (node (ref "J7") (pin "5") (pinfunction "5_5") (pintype "passive"))
      (node (ref "J7") (pin "6") (pinfunction "6_6") (pintype "passive"))
      (node (ref "J7") (pin "7") (pinfunction "7_7") (pintype "passive"))
      (node (ref "J7") (pin "8") (pinfunction "8_8") (pintype "passive"))
      (node (ref "J7") (pin "9") (pinfunction "9_9") (pintype "passive"))
      (node (ref "J9") (pin "1") (pinfunction "1_1") (pintype "passive"))
      (node (ref "MH1") (pin "1") (pinfunction "1_1") (pintype "passive"))
      (node (ref "MH2") (pin "1") (pinfunction "1_1") (pintype "passive"))
      (node (ref "MH3") (pin "1") (pinfunction "1_1") (pintype "passive"))
      (node (ref "R12") (pin "1") (pinfunction "1_1") (pintype "passive"))
      (node (ref "R8") (pin "2") (pinfunction "2_2") (pintype "passive"))
      (node (ref "SW1") (pin "3") (pinfunction "3_3") (pintype "passive"))
      (node (ref "SW1") (pin "4") (pinfunction "4_4") (pintype "passive"))
      (node (ref "SW2") (pin "3") (pinfunction "3_3") (pintype "passive"))
      (node (ref "SW2") (pin "4") (pinfunction "4_4") (pintype "passive"))
      (node (ref "U1") (pin "22") (pinfunction "GND_22") (pintype "passive"))
      (node (ref "U1") (pin "8") (pinfunction "GND_8") (pintype "passive"))
      (node (ref "U2") (pin "28") (pinfunction "UGND_28") (pintype "passive"))
      (node (ref "U2") (pin "3") (pinfunction "GND_3") (pintype "passive"))
      (node (ref "U3") (pin "3") (pinfunction "GND_3") (pintype "passive"))
      (node (ref "U3") (pin "6") (pinfunction "EPAD_6") (pintype "passive"))
      (node (ref "U4") (pin "3") (pinfunction "3_3") (pintype "passive"))
      (node (ref "U5") (pin "3") (pinfunction "3_3") (pintype "passive"))
      (node (ref "U6") (pin "3") (pinfunction "3_3") (pintype "passive"))
      (node (ref "U7") (pin "3") (pinfunction "3_3") (pintype "passive"))
      (node (ref "Z1") (pin "1") (pinfunction "1_1") (pintype "passive"))
      (node (ref "Z2") (pin "1") (pinfunction "1_1") (pintype "passive"))
    )
    (net (code "62") (name "Net-(C11-Pad2)") (class "Default")
      (node (ref "C11") (pin "2") (pinfunction "2_2") (pintype "passive"))
      (node (ref "JP1") (pin "1") (pinfunction "1_1") (pintype "passive"))
    )
    (net (code "63") (name "Net-(D1-Anode)") (class "Default")
      (node (ref "D1") (pin "2") (pinfunction "Anode_2") (pintype "passive"))
      (node (ref "R17") (pin "1") (pinfunction "1_1") (pintype "passive"))
    )
    (net (code "64") (name "Net-(D2-Anode)") (class "Default")
      (node (ref "D2") (pin "2") (pinfunction "Anode_2") (pintype "passive"))
      (node (ref "R15") (pin "1") (pinfunction "1_1") (pintype "passive"))
    )
    (net (code "65") (name "Net-(D2-Cathode)") (class "Default")
      (node (ref "D2") (pin "1") (pinfunction "Cathode_1") (pintype "passive"))
      (node (ref "U4") (pin "4") (pinfunction "4_4") (pintype "passive"))
    )
    (net (code "66") (name "Net-(D3-Anode)") (class "Default")
      (node (ref "D3") (pin "2") (pinfunction "Anode_2") (pintype "passive"))
      (node (ref "R2") (pin "1") (pinfunction "1_1") (pintype "passive"))
    )
    (net (code "67") (name "Net-(D4-Anode)") (class "Default")
      (node (ref "D4") (pin "2") (pinfunction "Anode_2") (pintype "passive"))
      (node (ref "R3") (pin "1") (pinfunction "1_1") (pintype "passive"))
    )
    (net (code "68") (name "Net-(D5-Anode)") (class "Default")
      (node (ref "D5") (pin "2") (pinfunction "Anode_2") (pintype "passive"))
      (node (ref "R19") (pin "1") (pinfunction "1_1") (pintype "passive"))
      (node (ref "R23") (pin "1") (pinfunction "1_1") (pintype "passive"))
    )
    (net (code "69") (name "Net-(J7-Pad4)") (class "Default")
      (node (ref "J7") (pin "4") (pinfunction "4_4") (pintype "passive"))
      (node (ref "R8") (pin "1") (pinfunction "1_1") (pintype "passive"))
    )
    (net (code "70") (name "Net-(JP1-Pad3)") (class "Default")
      (node (ref "JP1") (pin "3") (pinfunction "3_3") (pintype "passive"))
      (node (ref "R12") (pin "2") (pinfunction "2_2") (pintype "passive"))
    )
    (net (code "71") (name "Net-(R22-Pad1)") (class "Default")
      (node (ref "R22") (pin "1") (pinfunction "1_1") (pintype "passive"))
      (node (ref "U7") (pin "4") (pinfunction "4_4") (pintype "passive"))
    )
    (net (code "72") (name "unconnected-(J1-Pad1)") (class "Default")
      (node (ref "J1") (pin "1") (pinfunction "1_1") (pintype "passive+no_connect"))
    )
    (net (code "73") (name "unconnected-(J1-Pad8)") (class "Default")
      (node (ref "J1") (pin "8") (pinfunction "8_8") (pintype "passive+no_connect"))
    )
    (net (code "74") (name "unconnected-(MH4-Pad1)") (class "Default")
      (node (ref "MH4") (pin "1") (pinfunction "1_1") (pintype "passive+no_connect"))
    )
    (net (code "75") (name "unconnected-(U2-PB0_(~{SS}_{slash}_PCINT0)-Pad14)") (class "Default")
      (node (ref "U2") (pin "14") (pinfunction "PB0_(~{SS}_/_PCINT0)_14") (pintype "passive+no_connect"))
    )
    (net (code "76") (name "unconnected-(U2-PC2_(PCINT11_{slash}AIN2_)-Pad5)") (class "Default")
      (node (ref "U2") (pin "5") (pinfunction "PC2_(PCINT11_/AIN2_)_5") (pintype "passive+no_connect"))
    )
    (net (code "77") (name "unconnected-(U2-PC4_(PCINT10)-Pad26)") (class "Default")
      (node (ref "U2") (pin "26") (pinfunction "PC4_(PCINT10)_26") (pintype "passive+no_connect"))
    )
    (net (code "78") (name "unconnected-(U2-PC5_(_PCINT9{slash}_OC.1B)-Pad25)") (class "Default")
      (node (ref "U2") (pin "25") (pinfunction "PC5_(_PCINT9/_OC.1B)_25") (pintype "passive+no_connect"))
    )
    (net (code "79") (name "unconnected-(U2-PC6_(OC.1A_{slash}_PCINT8)-Pad23)") (class "Default")
      (node (ref "U2") (pin "23") (pinfunction "PC6_(OC.1A_/_PCINT8)_23") (pintype "passive+no_connect"))
    )
    (net (code "80") (name "unconnected-(U2-PC7_(INT4_{slash}_ICP1_{slash}_CLKO)-Pad22)") (class "Default")
      (node (ref "U2") (pin "22") (pinfunction "PC7_(INT4_/_ICP1_/_CLKO)_22") (pintype "passive+no_connect"))
    )
    (net (code "81") (name "unconnected-(U2-PD0_(OC.0B_{slash}_INT0)-Pad6)") (class "Default")
      (node (ref "U2") (pin "6") (pinfunction "PD0_(OC.0B_/_INT0)_6") (pintype "passive+no_connect"))
    )
    (net (code "82") (name "unconnected-(U2-PD1_(AIN0_{slash}_INT1)-Pad7)") (class "Default")
      (node (ref "U2") (pin "7") (pinfunction "PD1_(AIN0_/_INT1)_7") (pintype "passive+no_connect"))
    )
    (net (code "83") (name "unconnected-(U2-PD6_(~{RTS}_{slash}_AIN5_{slash}_INT6)-Pad12)") (class "Default")
      (node (ref "U2") (pin "12") (pinfunction "PD6_(~{RTS}_/_AIN5_/_INT6)_12") (pintype "passive+no_connect"))
    )
  )
)
